# ReuseBlock_ldo_2025-06-27.net
KiCad netlist of a schematic drawn in EasyEDA Pro
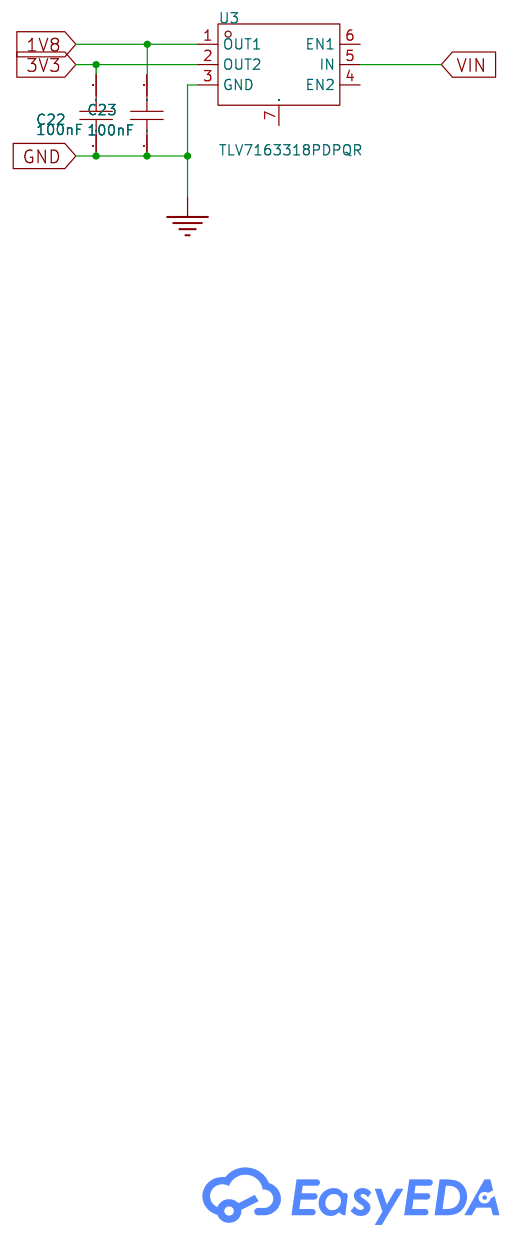
[diagram p0: schematic sheet]

(export (version "E")
  (design (tool "Eeschema 10.0.6"))
  (components
    (comp (ref "C22")
      (value "100nF")
      (footprint "easyedapro:C0201")
      (description "Capacitance:100nF Tolerance:±10% Tolerance:±10% Voltage Rating:10V Temperature Coefficient:X5R")
      (fields
        (field (name "Manufacturer Part") "C0201X5R104K100NTA")
        (field (name "Manufacturer") "EYANG(宇阳科技)")
      )
      (libsource (lib "easyedapro") (part "C0201X5R104K100NTA"))
    )
    (comp (ref "C23")
      (value "100nF")
      (footprint "easyedapro:C0201")
      (description "Capacitance:100nF Tolerance:±10% Tolerance:±10% Voltage Rating:10V Temperature Coefficient:X5R")
      (fields
        (field (name "Manufacturer Part") "C0201X5R104K100NTA")
        (field (name "Manufacturer") "EYANG(宇阳科技)")
      )
      (libsource (lib "easyedapro") (part "C0201X5R104K100NTA"))
    )
    (comp (ref "U3")
      (value "TLV7163318PDPQR")
      (footprint "easyedapro:XDFN-6_L1.2-W1.2-P0.40-BL-EP")
      (fields (field (name "Manufacturer") "TI(德州仪器)"))
      (libsource (lib "easyedapro") (part "TLV7163318PDPQR"))
    )
  )
  (nets
    (net (code "1") (name "1V8") (class "Default")
      (node (ref "U3") (pin "1") (pinfunction "OUT1_1") (pintype "unspecified"))
    )
    (net (code "2") (name "3V3") (class "Default")
      (node (ref "C22") (pin "2") (pinfunction "2_2") (pintype "unspecified"))
      (node (ref "U3") (pin "2") (pinfunction "OUT2_2") (pintype "unspecified"))
    )
    (net (code "3") (name "GND") (class "Default")
      (node (ref "C22") (pin "1") (pinfunction "1_1") (pintype "unspecified"))
      (node (ref "C23") (pin "1") (pinfunction "1_1") (pintype "unspecified"))
      (node (ref "U3") (pin "3") (pinfunction "GND_3") (pintype "unspecified"))
    )
    (net (code "4") (name "VIN") (class "Default")
      (node (ref "U3") (pin "5") (pinfunction "IN_5") (pintype "unspecified"))
    )
    (net (code "5") (name "unconnected-(C23-Pad2)") (class "Default")
      (node (ref "C23") (pin "2") (pinfunction "2_2") (pintype "unspecified"))
    )
    (net (code "6") (name "unconnected-(U3-EN1-Pad6)") (class "Default")
      (node (ref "U3") (pin "6") (pinfunction "EN1_6") (pintype "unspecified"))
    )
    (net (code "7") (name "unconnected-(U3-EN2-Pad4)") (class "Default")
      (node (ref "U3") (pin "4") (pinfunction "EN2_4") (pintype "unspecified"))
    )
    (net (code "8") (name "unconnected-(U3-EP-Pad7)") (class "Default")
      (node (ref "U3") (pin "7") (pinfunction "EP_7") (pintype "unspecified"))
    )
  )
)
